# gatedriver_trafo_sma_compact_SMD.net
KiCad netlist of a schematic drawn in EAGLE
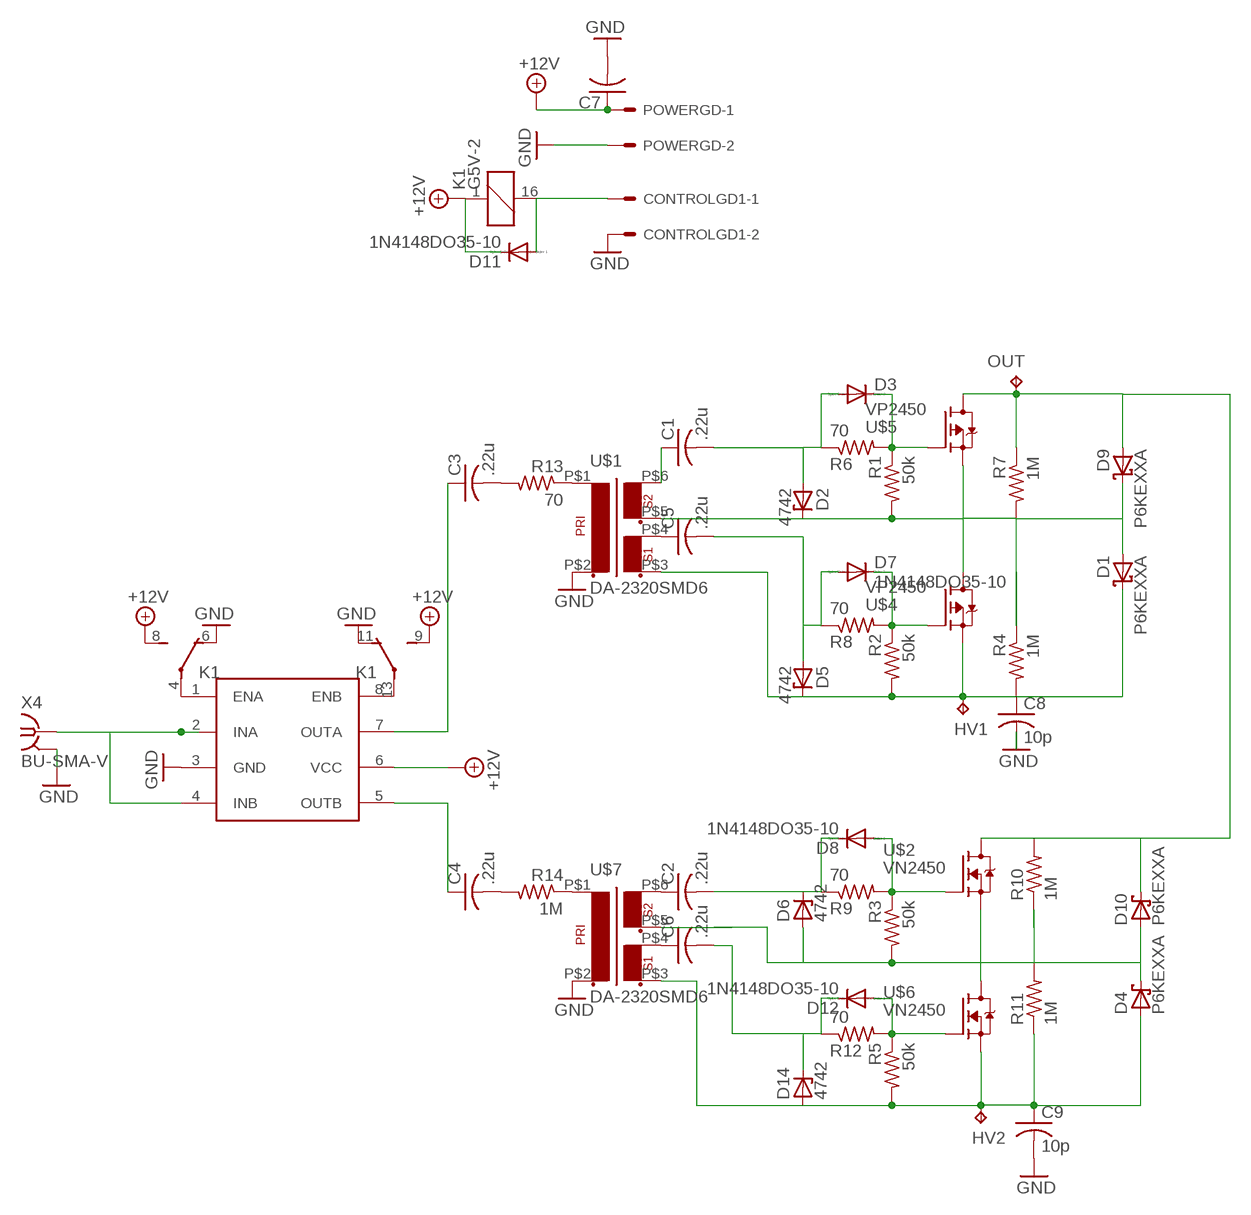
[diagram p0: schematic, sheet 1]

(export (version "E")
  (design (tool "Eeschema 10.0.6"))
  (components
    (comp (ref "C1")
      (value ".22u")
      (footprint "eagle-import:C0805")
      (libsource (lib "eagle-import") (part "resistor_C-USC0805"))
    )
    (comp (ref "C2")
      (value ".22u")
      (footprint "eagle-import:C050-055X075")
      (libsource (lib "eagle-import") (part "resistor_C-US050-055X075"))
    )
    (comp (ref "C3")
      (value ".22u")
      (footprint "eagle-import:C050-055X075")
      (libsource (lib "eagle-import") (part "resistor_C-US050-055X075"))
    )
    (comp (ref "C4")
      (value ".22u")
      (footprint "eagle-import:C050-055X075")
      (libsource (lib "eagle-import") (part "resistor_C-US050-055X075"))
    )
    (comp (ref "C5")
      (value ".22u")
      (footprint "eagle-import:C050-055X075")
      (libsource (lib "eagle-import") (part "resistor_C-US050-055X075"))
    )
    (comp (ref "C6")
      (value ".22u")
      (footprint "eagle-import:C050-055X075")
      (libsource (lib "eagle-import") (part "resistor_C-US050-055X075"))
    )
    (comp (ref "C7")
      (value "C-US050-030X075")
      (footprint "eagle-import:C050-030X075")
      (libsource (lib "eagle-import") (part "C-US050-030X075"))
    )
    (comp (ref "C8")
      (value "10p")
      (footprint "eagle-import:C102-064X133")
      (libsource (lib "eagle-import") (part "resistor_C-US102-064X133"))
    )
    (comp (ref "C9")
      (value "10p")
      (footprint "eagle-import:C102-064X133")
      (libsource (lib "eagle-import") (part "resistor_C-US102-064X133"))
    )
    (comp (ref "CONTROLGD1")
      (value "KK-156-2")
      (footprint "eagle-import:KK-156-2")
      (libsource (lib "eagle-import") (part "KK-156-2"))
    )
    (comp (ref "D1")
      (value "P6KEXXA")
      (footprint "eagle-import:C1702-15")
      (libsource (lib "eagle-import") (part "P6KEXXA"))
    )
    (comp (ref "D2")
      (value "4742")
      (footprint "eagle-import:SMB")
      (libsource (lib "eagle-import") (part "ZENER-DIODESMB"))
    )
    (comp (ref "D3")
      (value "DIODE-DO214AA")
      (footprint "eagle-import:DO214AA")
      (libsource (lib "eagle-import") (part "DIODE-DO214AA"))
    )
    (comp (ref "D4")
      (value "P6KEXXA")
      (footprint "eagle-import:C1702-15")
      (libsource (lib "eagle-import") (part "P6KEXXA"))
    )
    (comp (ref "D5")
      (value "4742")
      (footprint "eagle-import:ZDIO-10")
      (libsource (lib "eagle-import") (part "ZENER-DIODEZD-10"))
    )
    (comp (ref "D6")
      (value "4742")
      (footprint "eagle-import:ZDIO-10")
      (libsource (lib "eagle-import") (part "ZENER-DIODEZD-10"))
    )
    (comp (ref "D7")
      (value "1N4148DO35-10")
      (footprint "eagle-import:DO35-10")
      (libsource (lib "eagle-import") (part "1N4148DO35-10"))
    )
    (comp (ref "D8")
      (value "1N4148DO35-10")
      (footprint "eagle-import:DO35-10")
      (libsource (lib "eagle-import") (part "1N4148DO35-10"))
    )
    (comp (ref "D9")
      (value "P6KEXXA")
      (footprint "eagle-import:C1702-15")
      (libsource (lib "eagle-import") (part "P6KEXXA"))
    )
    (comp (ref "D10")
      (value "P6KEXXA")
      (footprint "eagle-import:C1702-15")
      (libsource (lib "eagle-import") (part "P6KEXXA"))
    )
    (comp (ref "D11")
      (value "1N4148DO35-10")
      (footprint "eagle-import:DO35-10")
      (libsource (lib "eagle-import") (part "1N4148DO35-10"))
    )
    (comp (ref "D12")
      (value "1N4148DO35-10")
      (footprint "eagle-import:DO35-10")
      (libsource (lib "eagle-import") (part "1N4148DO35-10"))
    )
    (comp (ref "D14")
      (value "4742")
      (footprint "eagle-import:ZDIO-10")
      (libsource (lib "eagle-import") (part "ZENER-DIODEZD-10"))
    )
    (comp (ref "HV1")
      (value "TPPAD1-20Y")
      (footprint "eagle-import:P1-20Y")
      (libsource (lib "eagle-import") (part "TPPAD1-20Y"))
    )
    (comp (ref "HV2")
      (value "TPPAD1-20Y")
      (footprint "eagle-import:P1-20Y")
      (libsource (lib "eagle-import") (part "TPPAD1-20Y"))
    )
    (comp (ref "K1")
      (value "G5V-2")
      (footprint "eagle-import:G5V-2")
      (fields (field (name "MPN") "G5V-2 5DC"))
      (libsource (lib "eagle-import") (part "G5V-2"))
    )
    (comp (ref "OUT")
      (value "TPPAD1-20Y")
      (footprint "eagle-import:P1-20Y")
      (libsource (lib "eagle-import") (part "TPPAD1-20Y"))
    )
    (comp (ref "POWERGD")
      (value "KK-156-2")
      (footprint "eagle-import:KK-156-2")
      (libsource (lib "eagle-import") (part "KK-156-2"))
    )
    (comp (ref "R1")
      (value "50k")
      (footprint "eagle-import:M0805")
      (libsource (lib "eagle-import") (part "R-US_M0805"))
    )
    (comp (ref "R2")
      (value "50k")
      (footprint "eagle-import:0207_10")
      (libsource (lib "eagle-import") (part "R-US_0207/10"))
    )
    (comp (ref "R3")
      (value "50k")
      (footprint "eagle-import:0207_10")
      (libsource (lib "eagle-import") (part "R-US_0207/10"))
    )
    (comp (ref "R4")
      (value "1M")
      (footprint "eagle-import:0207_10")
      (libsource (lib "eagle-import") (part "R-US_0207/10"))
    )
    (comp (ref "R5")
      (value "50k")
      (footprint "eagle-import:0207_10")
      (libsource (lib "eagle-import") (part "R-US_0207/10"))
    )
    (comp (ref "R6")
      (value "70")
      (footprint "eagle-import:R0805")
      (libsource (lib "eagle-import") (part "R-US_R0805"))
    )
    (comp (ref "R7")
      (value "1M")
      (footprint "eagle-import:0207_10")
      (libsource (lib "eagle-import") (part "R-US_0207/10"))
    )
    (comp (ref "R8")
      (value "70")
      (footprint "eagle-import:0207_10")
      (libsource (lib "eagle-import") (part "R-US_0207/10"))
    )
    (comp (ref "R9")
      (value "70")
      (footprint "eagle-import:0207_10")
      (libsource (lib "eagle-import") (part "R-US_0207/10"))
    )
    (comp (ref "R10")
      (value "1M")
      (footprint "eagle-import:0207_10")
      (libsource (lib "eagle-import") (part "R-US_0207/10"))
    )
    (comp (ref "R11")
      (value "1M")
      (footprint "eagle-import:0207_10")
      (libsource (lib "eagle-import") (part "R-US_0207/10"))
    )
    (comp (ref "R12")
      (value "70")
      (footprint "eagle-import:0207_10")
      (libsource (lib "eagle-import") (part "R-US_0207/10"))
    )
    (comp (ref "R13")
      (value "70")
      (footprint "eagle-import:0207_10")
      (libsource (lib "eagle-import") (part "R-US_0207/10"))
    )
    (comp (ref "R14")
      (value "1M")
      (footprint "eagle-import:0207_10")
      (libsource (lib "eagle-import") (part "R-US_0207/10"))
    )
    (comp (ref "U$1")
      (value "DA-2320SMD6")
      (footprint "eagle-import:SMD6")
      (libsource (lib "eagle-import") (part "DA-2320SMD6"))
    )
    (comp (ref "U$2")
      (value "VN2450")
      (footprint "eagle-import:SOT89-BCE")
      (libsource (lib "eagle-import") (part "VN2450"))
    )
    (comp (ref "U$3")
      (value "UCC27425")
      (footprint "eagle-import:DIL08")
      (libsource (lib "eagle-import") (part "UCC27425"))
    )
    (comp (ref "U$4")
      (value "VP2450")
      (footprint "eagle-import:SOT89-BCE")
      (libsource (lib "eagle-import") (part "VP2450"))
    )
    (comp (ref "U$5")
      (value "VP2450")
      (footprint "eagle-import:SOT89-BCE")
      (libsource (lib "eagle-import") (part "VP2450"))
    )
    (comp (ref "U$6")
      (value "VN2450")
      (footprint "eagle-import:SOT89-BCE")
      (libsource (lib "eagle-import") (part "VN2450"))
    )
    (comp (ref "U$7")
      (value "DA-2320SMD6")
      (footprint "eagle-import:SMD6")
      (libsource (lib "eagle-import") (part "DA-2320SMD6"))
    )
    (comp (ref "X4")
      (value "BU-SMA-V")
      (footprint "eagle-import:BU-SMA-V")
      (libsource (lib "eagle-import") (part "BU-SMA-V"))
    )
  )
  (nets
    (net (code "1") (name "+12V") (class "Default")
      (node (ref "C7") (pin "1") (pinfunction "1_1") (pintype "passive"))
      (node (ref "D11") (pin "C") (pinfunction "C_C") (pintype "passive"))
      (node (ref "K1") (pin "1") (pinfunction "1_1") (pintype "passive"))
      (node (ref "K1") (pin "8") (pinfunction "S_8") (pintype "passive"))
      (node (ref "K1") (pin "9") (pinfunction "S_9") (pintype "passive"))
      (node (ref "POWERGD") (pin "1") (pinfunction "S_1") (pintype "passive"))
      (node (ref "U$3") (pin "6") (pinfunction "VCC_6") (pintype "bidirectional"))
    )
    (net (code "2") (name "GND") (class "Default")
      (node (ref "C7") (pin "2") (pinfunction "2_2") (pintype "passive"))
      (node (ref "C8") (pin "2") (pinfunction "2_2") (pintype "passive"))
      (node (ref "C9") (pin "2") (pinfunction "2_2") (pintype "passive"))
      (node (ref "CONTROLGD1") (pin "2") (pinfunction "S_2") (pintype "passive"))
      (node (ref "K1") (pin "11") (pinfunction "O_11") (pintype "passive"))
      (node (ref "K1") (pin "6") (pinfunction "O_6") (pintype "passive"))
      (node (ref "POWERGD") (pin "2") (pinfunction "S_2") (pintype "passive"))
      (node (ref "U$1") (pin "P$2") (pinfunction "2_P$2") (pintype "passive"))
      (node (ref "U$3") (pin "3") (pinfunction "GND_3") (pintype "bidirectional"))
      (node (ref "U$7") (pin "P$2") (pinfunction "2_P$2") (pintype "passive"))
      (node (ref "X4") (pin "2") (pinfunction "2_2") (pintype "passive"))
      (node (ref "X4") (pin "3") (pinfunction "2_3") (pintype "passive"))
      (node (ref "X4") (pin "4") (pinfunction "2_4") (pintype "passive"))
      (node (ref "X4") (pin "5") (pinfunction "2_5") (pintype "passive"))
    )
    (net (code "3") (name "Net-(C1-Pad2)") (class "Default")
      (node (ref "C1") (pin "2") (pinfunction "2_2") (pintype "passive"))
      (node (ref "D2") (pin "A") (pinfunction "A_A") (pintype "passive"))
      (node (ref "D3") (pin "A") (pinfunction "A_A") (pintype "passive"))
      (node (ref "R6") (pin "1") (pinfunction "1_1") (pintype "passive"))
    )
    (net (code "4") (name "Net-(C2-Pad2)") (class "Default")
      (node (ref "C2") (pin "2") (pinfunction "2_2") (pintype "passive"))
      (node (ref "D6") (pin "C") (pinfunction "C_C") (pintype "passive"))
      (node (ref "D8") (pin "C") (pinfunction "C_C") (pintype "passive"))
      (node (ref "R9") (pin "1") (pinfunction "1_1") (pintype "passive"))
    )
    (net (code "5") (name "Net-(C3-Pad2)") (class "Default")
      (node (ref "C3") (pin "2") (pinfunction "2_2") (pintype "passive"))
      (node (ref "R13") (pin "2") (pinfunction "2_2") (pintype "passive"))
    )
    (net (code "6") (name "Net-(C4-Pad2)") (class "Default")
      (node (ref "C4") (pin "2") (pinfunction "2_2") (pintype "passive"))
      (node (ref "R14") (pin "2") (pinfunction "2_2") (pintype "passive"))
    )
    (net (code "7") (name "Net-(C5-Pad2)") (class "Default")
      (node (ref "C5") (pin "2") (pinfunction "2_2") (pintype "passive"))
      (node (ref "D5") (pin "A") (pinfunction "A_A") (pintype "passive"))
      (node (ref "D7") (pin "A") (pinfunction "A_A") (pintype "passive"))
      (node (ref "R8") (pin "1") (pinfunction "1_1") (pintype "passive"))
    )
    (net (code "8") (name "Net-(C6-Pad2)") (class "Default")
      (node (ref "C6") (pin "2") (pinfunction "2_2") (pintype "passive"))
      (node (ref "D12") (pin "C") (pinfunction "C_C") (pintype "passive"))
      (node (ref "D14") (pin "C") (pinfunction "C_C") (pintype "passive"))
      (node (ref "R12") (pin "1") (pinfunction "1_1") (pintype "passive"))
    )
    (net (code "9") (name "Net-(CONTROLGD1A-S)") (class "Default")
      (node (ref "CONTROLGD1") (pin "1") (pinfunction "S_1") (pintype "passive"))
      (node (ref "D11") (pin "A") (pinfunction "A_A") (pintype "passive"))
      (node (ref "K1") (pin "16") (pinfunction "2_16") (pintype "passive"))
    )
    (net (code "10") (name "Net-(D10-PadC)") (class "Default")
      (node (ref "D10") (pin "C") (pinfunction "C_C") (pintype "passive"))
      (node (ref "D9") (pin "A") (pinfunction "A_A") (pintype "passive"))
      (node (ref "OUT") (pin "TP") (pinfunction "TP_TP") (pintype "input"))
      (node (ref "R10") (pin "2") (pinfunction "2_2") (pintype "passive"))
      (node (ref "R7") (pin "1") (pinfunction "1_1") (pintype "passive"))
      (node (ref "U$2") (pin "C") (pinfunction "D_C") (pintype "passive"))
      (node (ref "U$2") (pin "C@1") (pinfunction "D_C@1") (pintype "passive"))
      (node (ref "U$5") (pin "C") (pinfunction "D_C") (pintype "passive"))
      (node (ref "U$5") (pin "C@1") (pinfunction "D_C@1") (pintype "passive"))
    )
    (net (code "11") (name "Net-(K1A-P)") (class "Default")
      (node (ref "K1") (pin "4") (pinfunction "P_4") (pintype "passive"))
      (node (ref "U$3") (pin "1") (pinfunction "ENA_1") (pintype "bidirectional"))
    )
    (net (code "12") (name "Net-(K1B-P)") (class "Default")
      (node (ref "K1") (pin "13") (pinfunction "P_13") (pintype "passive"))
      (node (ref "U$3") (pin "8") (pinfunction "ENB_8") (pintype "bidirectional"))
    )
    (net (code "13") (name "Net-(U$1-1)") (class "Default")
      (node (ref "R13") (pin "1") (pinfunction "1_1") (pintype "passive"))
      (node (ref "U$1") (pin "P$1") (pinfunction "1_P$1") (pintype "passive"))
    )
    (net (code "14") (name "Net-(U$1-3)") (class "Default")
      (node (ref "C8") (pin "1") (pinfunction "1_1") (pintype "passive"))
      (node (ref "D1") (pin "C") (pinfunction "C_C") (pintype "passive"))
      (node (ref "D5") (pin "C") (pinfunction "C_C") (pintype "passive"))
      (node (ref "HV1") (pin "TP") (pinfunction "TP_TP") (pintype "input"))
      (node (ref "R2") (pin "2") (pinfunction "2_2") (pintype "passive"))
      (node (ref "R4") (pin "2") (pinfunction "2_2") (pintype "passive"))
      (node (ref "U$1") (pin "P$3") (pinfunction "3_P$3") (pintype "passive"))
      (node (ref "U$4") (pin "E") (pinfunction "S_E") (pintype "passive"))
    )
    (net (code "15") (name "Net-(U$1-4)") (class "Default")
      (node (ref "C5") (pin "1") (pinfunction "1_1") (pintype "passive"))
      (node (ref "U$1") (pin "P$4") (pinfunction "4_P$4") (pintype "passive"))
    )
    (net (code "16") (name "Net-(U$1-5)") (class "Default")
      (node (ref "D1") (pin "A") (pinfunction "A_A") (pintype "passive"))
      (node (ref "D2") (pin "C") (pinfunction "C_C") (pintype "passive"))
      (node (ref "D9") (pin "C") (pinfunction "C_C") (pintype "passive"))
      (node (ref "R1") (pin "2") (pinfunction "2_2") (pintype "passive"))
      (node (ref "R4") (pin "1") (pinfunction "1_1") (pintype "passive"))
      (node (ref "R7") (pin "2") (pinfunction "2_2") (pintype "passive"))
      (node (ref "U$1") (pin "P$5") (pinfunction "5_P$5") (pintype "passive"))
      (node (ref "U$4") (pin "C") (pinfunction "D_C") (pintype "passive"))
      (node (ref "U$4") (pin "C@1") (pinfunction "D_C@1") (pintype "passive"))
      (node (ref "U$5") (pin "E") (pinfunction "S_E") (pintype "passive"))
    )
    (net (code "17") (name "Net-(U$1-6)") (class "Default")
      (node (ref "C1") (pin "1") (pinfunction "1_1") (pintype "passive"))
      (node (ref "U$1") (pin "P$6") (pinfunction "6_P$6") (pintype "passive"))
    )
    (net (code "18") (name "Net-(U$2-G)") (class "Default")
      (node (ref "D8") (pin "A") (pinfunction "A_A") (pintype "passive"))
      (node (ref "R3") (pin "1") (pinfunction "1_1") (pintype "passive"))
      (node (ref "R9") (pin "2") (pinfunction "2_2") (pintype "passive"))
      (node (ref "U$2") (pin "B") (pinfunction "G_B") (pintype "passive"))
    )
    (net (code "19") (name "Net-(U$2-S)") (class "Default")
      (node (ref "D10") (pin "A") (pinfunction "A_A") (pintype "passive"))
      (node (ref "D4") (pin "C") (pinfunction "C_C") (pintype "passive"))
      (node (ref "D6") (pin "A") (pinfunction "A_A") (pintype "passive"))
      (node (ref "R10") (pin "1") (pinfunction "1_1") (pintype "passive"))
      (node (ref "R11") (pin "2") (pinfunction "2_2") (pintype "passive"))
      (node (ref "R3") (pin "2") (pinfunction "2_2") (pintype "passive"))
      (node (ref "U$2") (pin "E") (pinfunction "S_E") (pintype "passive"))
      (node (ref "U$6") (pin "C") (pinfunction "D_C") (pintype "passive"))
      (node (ref "U$6") (pin "C@1") (pinfunction "D_C@1") (pintype "passive"))
    )
    (net (code "20") (name "Net-(U$3-INA)") (class "Default")
      (node (ref "U$3") (pin "2") (pinfunction "INA_2") (pintype "bidirectional"))
      (node (ref "U$3") (pin "4") (pinfunction "INB_4") (pintype "bidirectional"))
      (node (ref "X4") (pin "1") (pinfunction "1_1") (pintype "passive"))
    )
    (net (code "21") (name "Net-(U$3-OUTA)") (class "Default")
      (node (ref "C3") (pin "1") (pinfunction "1_1") (pintype "passive"))
      (node (ref "U$3") (pin "7") (pinfunction "OUTA_7") (pintype "bidirectional"))
    )
    (net (code "22") (name "Net-(U$3-OUTB)") (class "Default")
      (node (ref "C4") (pin "1") (pinfunction "1_1") (pintype "passive"))
      (node (ref "U$3") (pin "5") (pinfunction "OUTB_5") (pintype "bidirectional"))
    )
    (net (code "23") (name "Net-(U$4-G)") (class "Default")
      (node (ref "D7") (pin "C") (pinfunction "C_C") (pintype "passive"))
      (node (ref "R2") (pin "1") (pinfunction "1_1") (pintype "passive"))
      (node (ref "R8") (pin "2") (pinfunction "2_2") (pintype "passive"))
      (node (ref "U$4") (pin "B") (pinfunction "G_B") (pintype "passive"))
    )
    (net (code "24") (name "Net-(U$5-G)") (class "Default")
      (node (ref "D3") (pin "C") (pinfunction "C_C") (pintype "passive"))
      (node (ref "R1") (pin "1") (pinfunction "1_1") (pintype "passive"))
      (node (ref "R6") (pin "2") (pinfunction "2_2") (pintype "passive"))
      (node (ref "U$5") (pin "B") (pinfunction "G_B") (pintype "passive"))
    )
    (net (code "25") (name "Net-(U$6-G)") (class "Default")
      (node (ref "D12") (pin "A") (pinfunction "A_A") (pintype "passive"))
      (node (ref "R12") (pin "2") (pinfunction "2_2") (pintype "passive"))
      (node (ref "R5") (pin "1") (pinfunction "1_1") (pintype "passive"))
      (node (ref "U$6") (pin "B") (pinfunction "G_B") (pintype "passive"))
    )
    (net (code "26") (name "Net-(U$6-S)") (class "Default")
      (node (ref "C9") (pin "1") (pinfunction "1_1") (pintype "passive"))
      (node (ref "D14") (pin "A") (pinfunction "A_A") (pintype "passive"))
      (node (ref "D4") (pin "A") (pinfunction "A_A") (pintype "passive"))
      (node (ref "HV2") (pin "TP") (pinfunction "TP_TP") (pintype "input"))
      (node (ref "R11") (pin "1") (pinfunction "1_1") (pintype "passive"))
      (node (ref "R5") (pin "2") (pinfunction "2_2") (pintype "passive"))
      (node (ref "U$6") (pin "E") (pinfunction "S_E") (pintype "passive"))
      (node (ref "U$7") (pin "P$3") (pinfunction "3_P$3") (pintype "passive"))
    )
    (net (code "27") (name "Net-(U$7-1)") (class "Default")
      (node (ref "R14") (pin "1") (pinfunction "1_1") (pintype "passive"))
      (node (ref "U$7") (pin "P$1") (pinfunction "1_P$1") (pintype "passive"))
    )
    (net (code "28") (name "Net-(U$7-4)") (class "Default")
      (node (ref "C6") (pin "1") (pinfunction "1_1") (pintype "passive"))
      (node (ref "U$7") (pin "P$4") (pinfunction "4_P$4") (pintype "passive"))
    )
    (net (code "29") (name "Net-(U$7-6)") (class "Default")
      (node (ref "C2") (pin "1") (pinfunction "1_1") (pintype "passive"))
      (node (ref "U$7") (pin "P$6") (pinfunction "6_P$6") (pintype "passive"))
    )
    (net (code "30") (name "unconnected-(U$7-5-PadP$5)") (class "Default")
      (node (ref "U$7") (pin "P$5") (pinfunction "5_P$5") (pintype "passive"))
    )
  )
)
